# io_b.net
KiCad netlist of a schematic drawn in Altium Designer
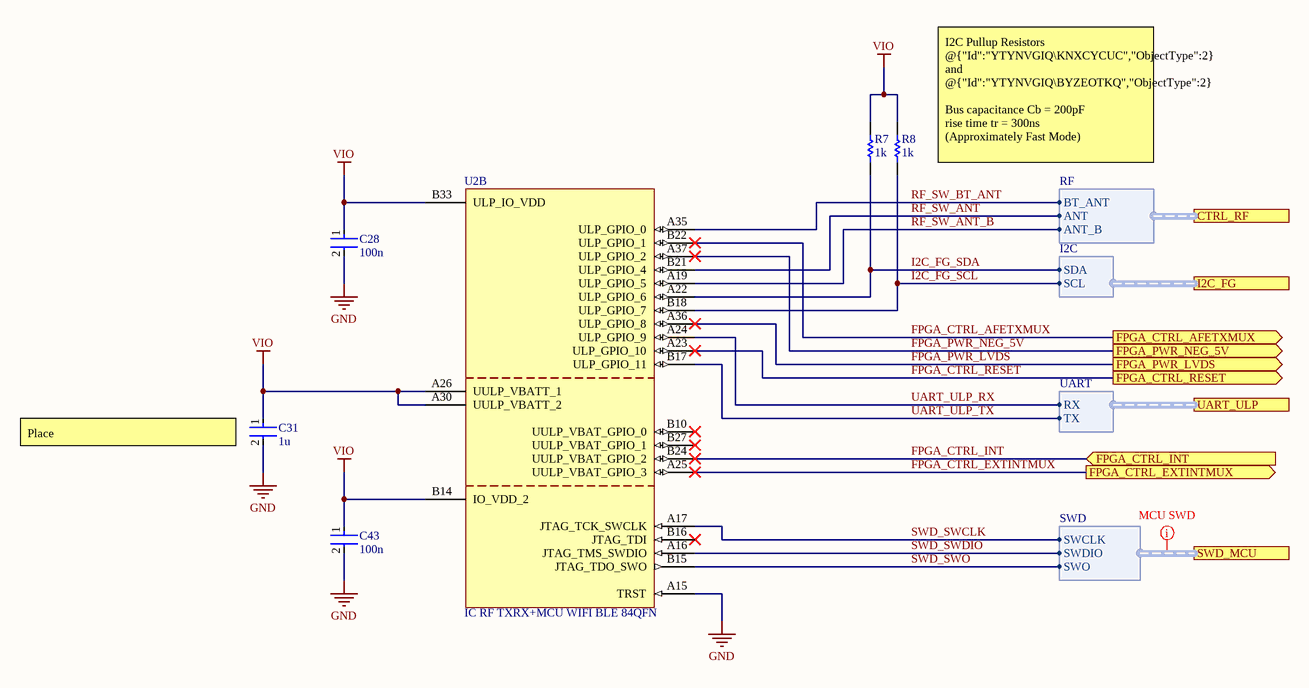
[diagram p0: io_b.SchDoc]

(export (version "E")
  (design (tool "Eeschema 10.0.6"))
  (components
    (comp (ref "C28")
      (value "100n")
      (footprint "FP-GRT155-0_05-MFG")
      (description "Multi-Layer Ceramic Capacitor 100nF 50V X7R ±10% 0402 Paper T/R")
      (libsource (lib "Altium Content Vault") (part "02cd4be3c70576c341d710602a673aa"))
    )
    (comp (ref "C31")
      (value "1u")
      (footprint "FP-GRM155-0_05-MFG")
      (description "Chip Multilayer Ceramic Capacitors for General Purpose, 0402, 1.0uF, X6S, 22%, 10%, 16V")
      (fields (field (name "TOLERANCE") "10%"))
      (libsource (lib "Altium Content Vault") (part "02cd4be3c70576c341d710602a673aa"))
    )
    (comp (ref "C43")
      (value "100n")
      (footprint "FP-GRT155-0_05-MFG")
      (description "Multi-Layer Ceramic Capacitor 100nF 50V X7R ±10% 0402 Paper T/R")
      (libsource (lib "Altium Content Vault") (part "02cd4be3c70576c341d710602a673aa"))
    )
    (comp (ref "R7")
      (value "1k")
      (footprint "RESC1005X40X25LL05T10")
      (fields (field (name "MANUFACTURER") "Yageo") (field (name "PART NUMBER") "RC0402FR-131KL"))
      (libsource (lib "Altium Content Vault") (part "RES"))
    )
    (comp (ref "R8")
      (value "1k")
      (footprint "RESC1005X40X25LL05T10")
      (fields (field (name "MANUFACTURER") "Yageo") (field (name "PART NUMBER") "RC0402FR-131KL"))
      (libsource (lib "Altium Content Vault") (part "RES"))
    )
    (comp (ref "U2")
      (value "IC RF TXRX+MCU WIFI BLE 84QFN")
      (footprint "wius:SIWG917M110LGTBA")
      (libsource (lib "wius") (part "SIWG917"))
    )
  )
  (nets
    (net (code "5") (name "/FPGA_CTRL_AFETXMUX") (class "Default")
      (node (ref "U2") (pin "B22") (pinfunction "ULP_GPIO_1_B22") (pintype "bidirectional+no_connect"))
    )
    (net (code "6") (name "/FPGA_CTRL_EXTINTMUX") (class "Default")
      (node (ref "U2") (pin "A25") (pinfunction "UULP_VBAT_GPIO_3_A25") (pintype "bidirectional+no_connect"))
    )
    (net (code "7") (name "/FPGA_CTRL_INT") (class "Default")
      (node (ref "U2") (pin "B24") (pinfunction "UULP_VBAT_GPIO_2_B24") (pintype "bidirectional+no_connect"))
    )
    (net (code "8") (name "/FPGA_CTRL_RESET") (class "Default")
      (node (ref "U2") (pin "A23") (pinfunction "ULP_GPIO_10_A23") (pintype "bidirectional+no_connect"))
    )
    (net (code "9") (name "/FPGA_PWR_LVDS") (class "Default")
      (node (ref "U2") (pin "A36") (pinfunction "ULP_GPIO_8_A36") (pintype "bidirectional+no_connect"))
    )
    (net (code "10") (name "/FPGA_PWR_NEG_5V") (class "Default")
      (node (ref "U2") (pin "A37") (pinfunction "ULP_GPIO_2_A37") (pintype "bidirectional+no_connect"))
    )
    (net (code "11") (name "/I2C_FG_SCL") (class "Default")
      (node (ref "R8") (pin "1") (pinfunction "1_1") (pintype "passive"))
      (node (ref "U2") (pin "B18") (pinfunction "ULP_GPIO_7_B18") (pintype "bidirectional"))
    )
    (net (code "12") (name "/I2C_FG_SDA") (class "Default")
      (node (ref "R7") (pin "1") (pinfunction "1_1") (pintype "passive"))
      (node (ref "U2") (pin "A22") (pinfunction "ULP_GPIO_6_A22") (pintype "bidirectional"))
    )
    (net (code "13") (name "/RF_SW_ANT") (class "Default")
      (node (ref "U2") (pin "B21") (pinfunction "ULP_GPIO_4_B21") (pintype "bidirectional"))
    )
    (net (code "14") (name "/RF_SW_ANT_B") (class "Default")
      (node (ref "U2") (pin "A19") (pinfunction "ULP_GPIO_5_A19") (pintype "bidirectional"))
    )
    (net (code "15") (name "/RF_SW_BT_ANT") (class "Default")
      (node (ref "U2") (pin "A35") (pinfunction "ULP_GPIO_0_A35") (pintype "bidirectional"))
    )
    (net (code "16") (name "/SWD_SWCLK") (class "Default")
      (node (ref "U2") (pin "A17") (pinfunction "JTAG_TCK_SWCLK_A17") (pintype "input"))
    )
    (net (code "17") (name "/SWD_SWDIO") (class "Default")
      (node (ref "U2") (pin "A16") (pinfunction "JTAG_TMS_SWDIO_A16") (pintype "input"))
    )
    (net (code "18") (name "/SWD_SWO") (class "Default")
      (node (ref "U2") (pin "B15") (pinfunction "JTAG_TDO_SWO_B15") (pintype "output"))
    )
    (net (code "19") (name "/UART_ULP_RX") (class "Default")
      (node (ref "U2") (pin "A24") (pinfunction "ULP_GPIO_9_A24") (pintype "bidirectional"))
    )
    (net (code "20") (name "/UART_ULP_TX") (class "Default")
      (node (ref "U2") (pin "B17") (pinfunction "ULP_GPIO_11_B17") (pintype "bidirectional"))
    )
    (net (code "25") (name "GND") (class "Default")
      (node (ref "C28") (pin "2") (pinfunction "2_2") (pintype "passive"))
      (node (ref "C31") (pin "2") (pinfunction "2_2") (pintype "passive"))
      (node (ref "C43") (pin "2") (pinfunction "2_2") (pintype "passive"))
      (node (ref "U2") (pin "A15") (pinfunction "TRST_A15") (pintype "input"))
    )
    (net (code "26") (name "VIO") (class "Default")
      (node (ref "C28") (pin "1") (pinfunction "1_1") (pintype "passive"))
      (node (ref "C31") (pin "1") (pinfunction "1_1") (pintype "passive"))
      (node (ref "C43") (pin "1") (pinfunction "1_1") (pintype "passive"))
      (node (ref "R7") (pin "2") (pinfunction "2_2") (pintype "passive"))
      (node (ref "R8") (pin "2") (pinfunction "2_2") (pintype "passive"))
      (node (ref "U2") (pin "A26") (pinfunction "UULP_VBATT_1_A26") (pintype "power_in"))
      (node (ref "U2") (pin "A30") (pinfunction "UULP_VBATT_2_A30") (pintype "power_in"))
      (node (ref "U2") (pin "B14") (pinfunction "IO_VDD_2_B14") (pintype "power_in"))
      (node (ref "U2") (pin "B33") (pinfunction "ULP_IO_VDD_B33") (pintype "power_in"))
    )
    (net (code "27") (name "unconnected-(U2B-JTAG_TDI-PadB16)") (class "Default")
      (node (ref "U2") (pin "B16") (pinfunction "JTAG_TDI_B16") (pintype "input+no_connect"))
    )
    (net (code "28") (name "unconnected-(U2B-UULP_VBAT_GPIO_0-PadB10)") (class "Default")
      (node (ref "U2") (pin "B10") (pinfunction "UULP_VBAT_GPIO_0_B10") (pintype "bidirectional+no_connect"))
    )
    (net (code "29") (name "unconnected-(U2B-UULP_VBAT_GPIO_1-PadB27)") (class "Default")
      (node (ref "U2") (pin "B27") (pinfunction "UULP_VBAT_GPIO_1_B27") (pintype "bidirectional+no_connect"))
    )
  )
)
